# Backplane-3.net
KiCad netlist of a schematic drawn in EAGLE
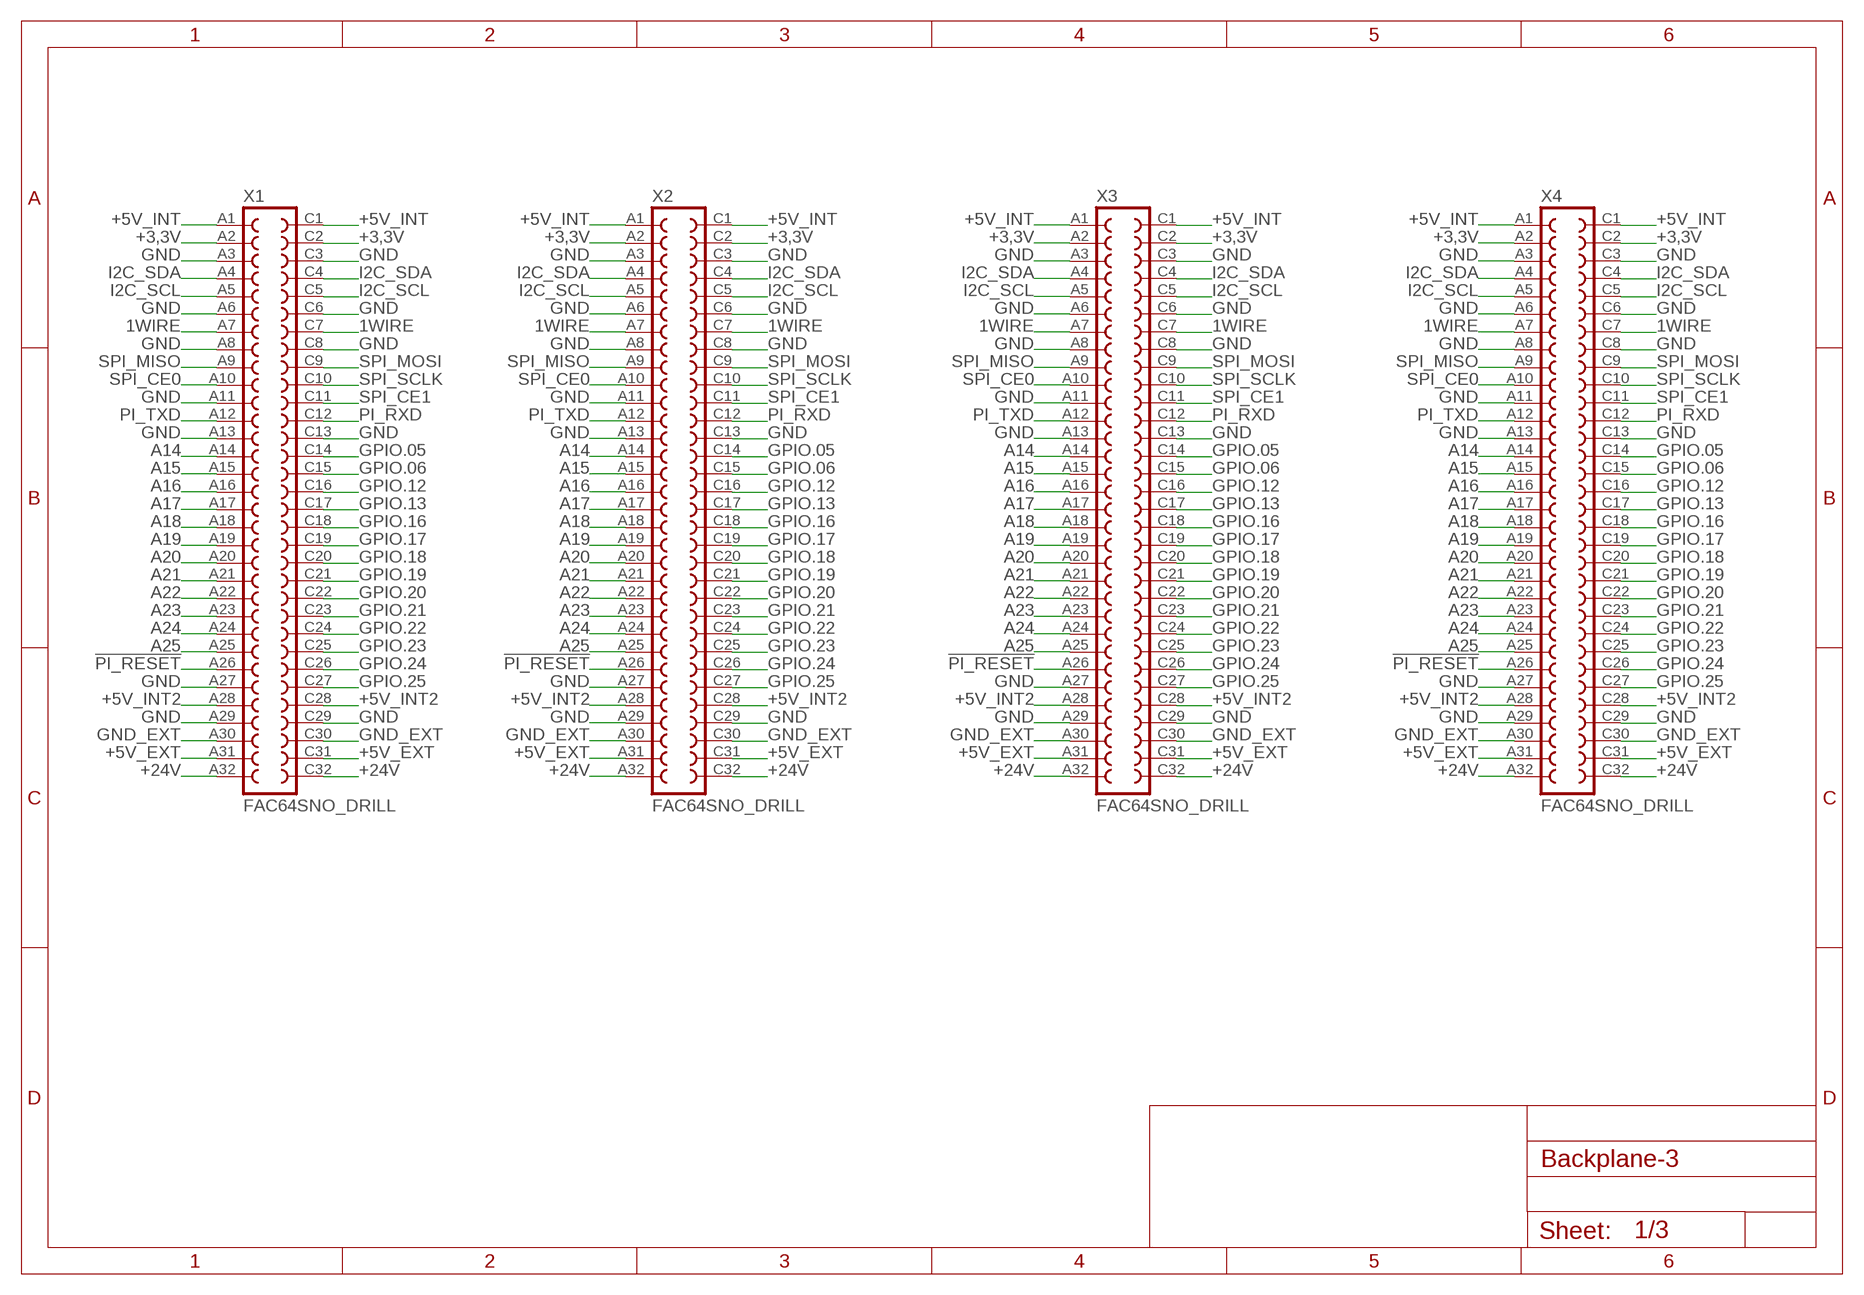
[diagram p0: schematic, sheet 1]
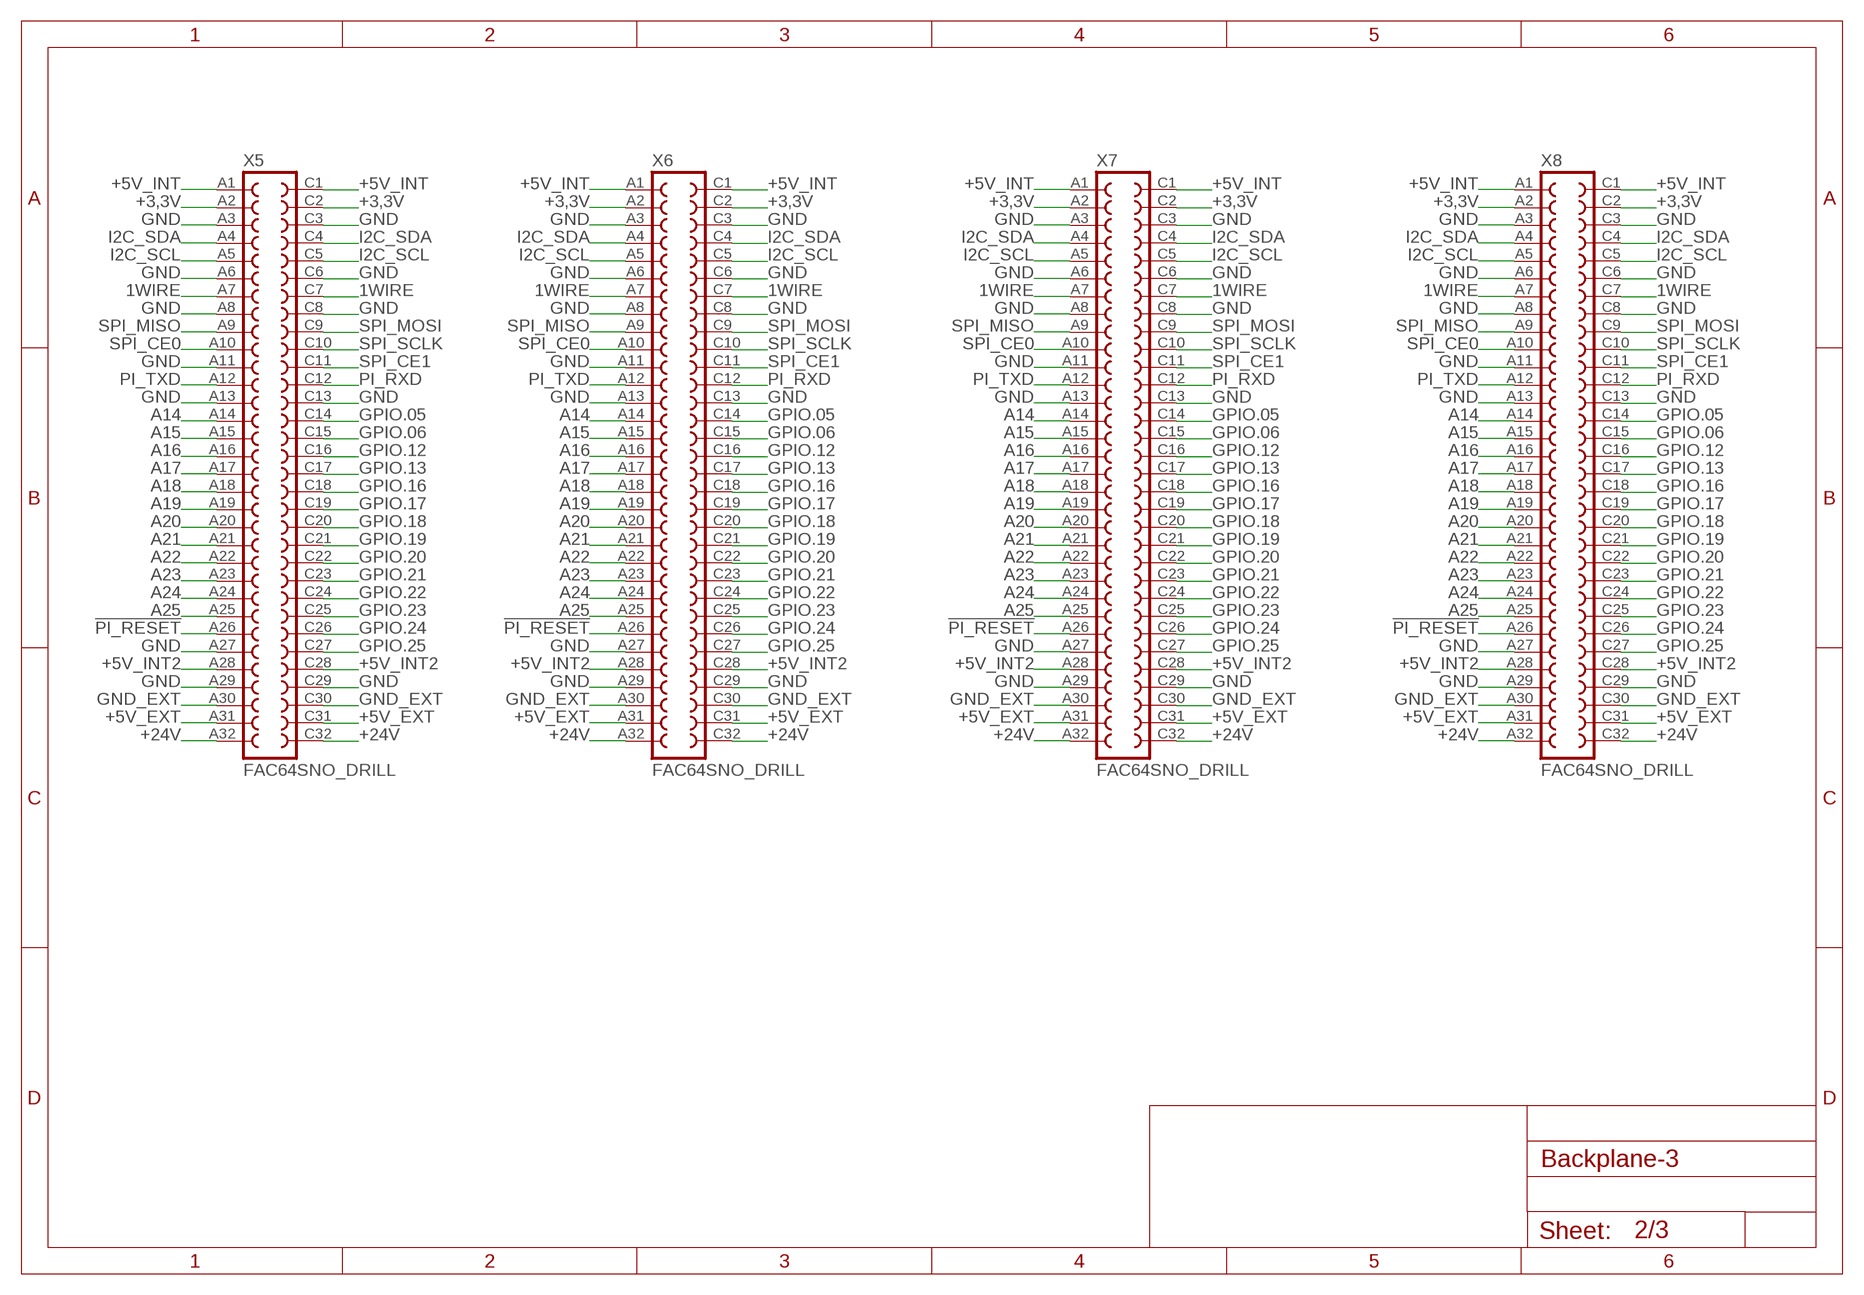
[diagram p1: schematic, sheet 2]
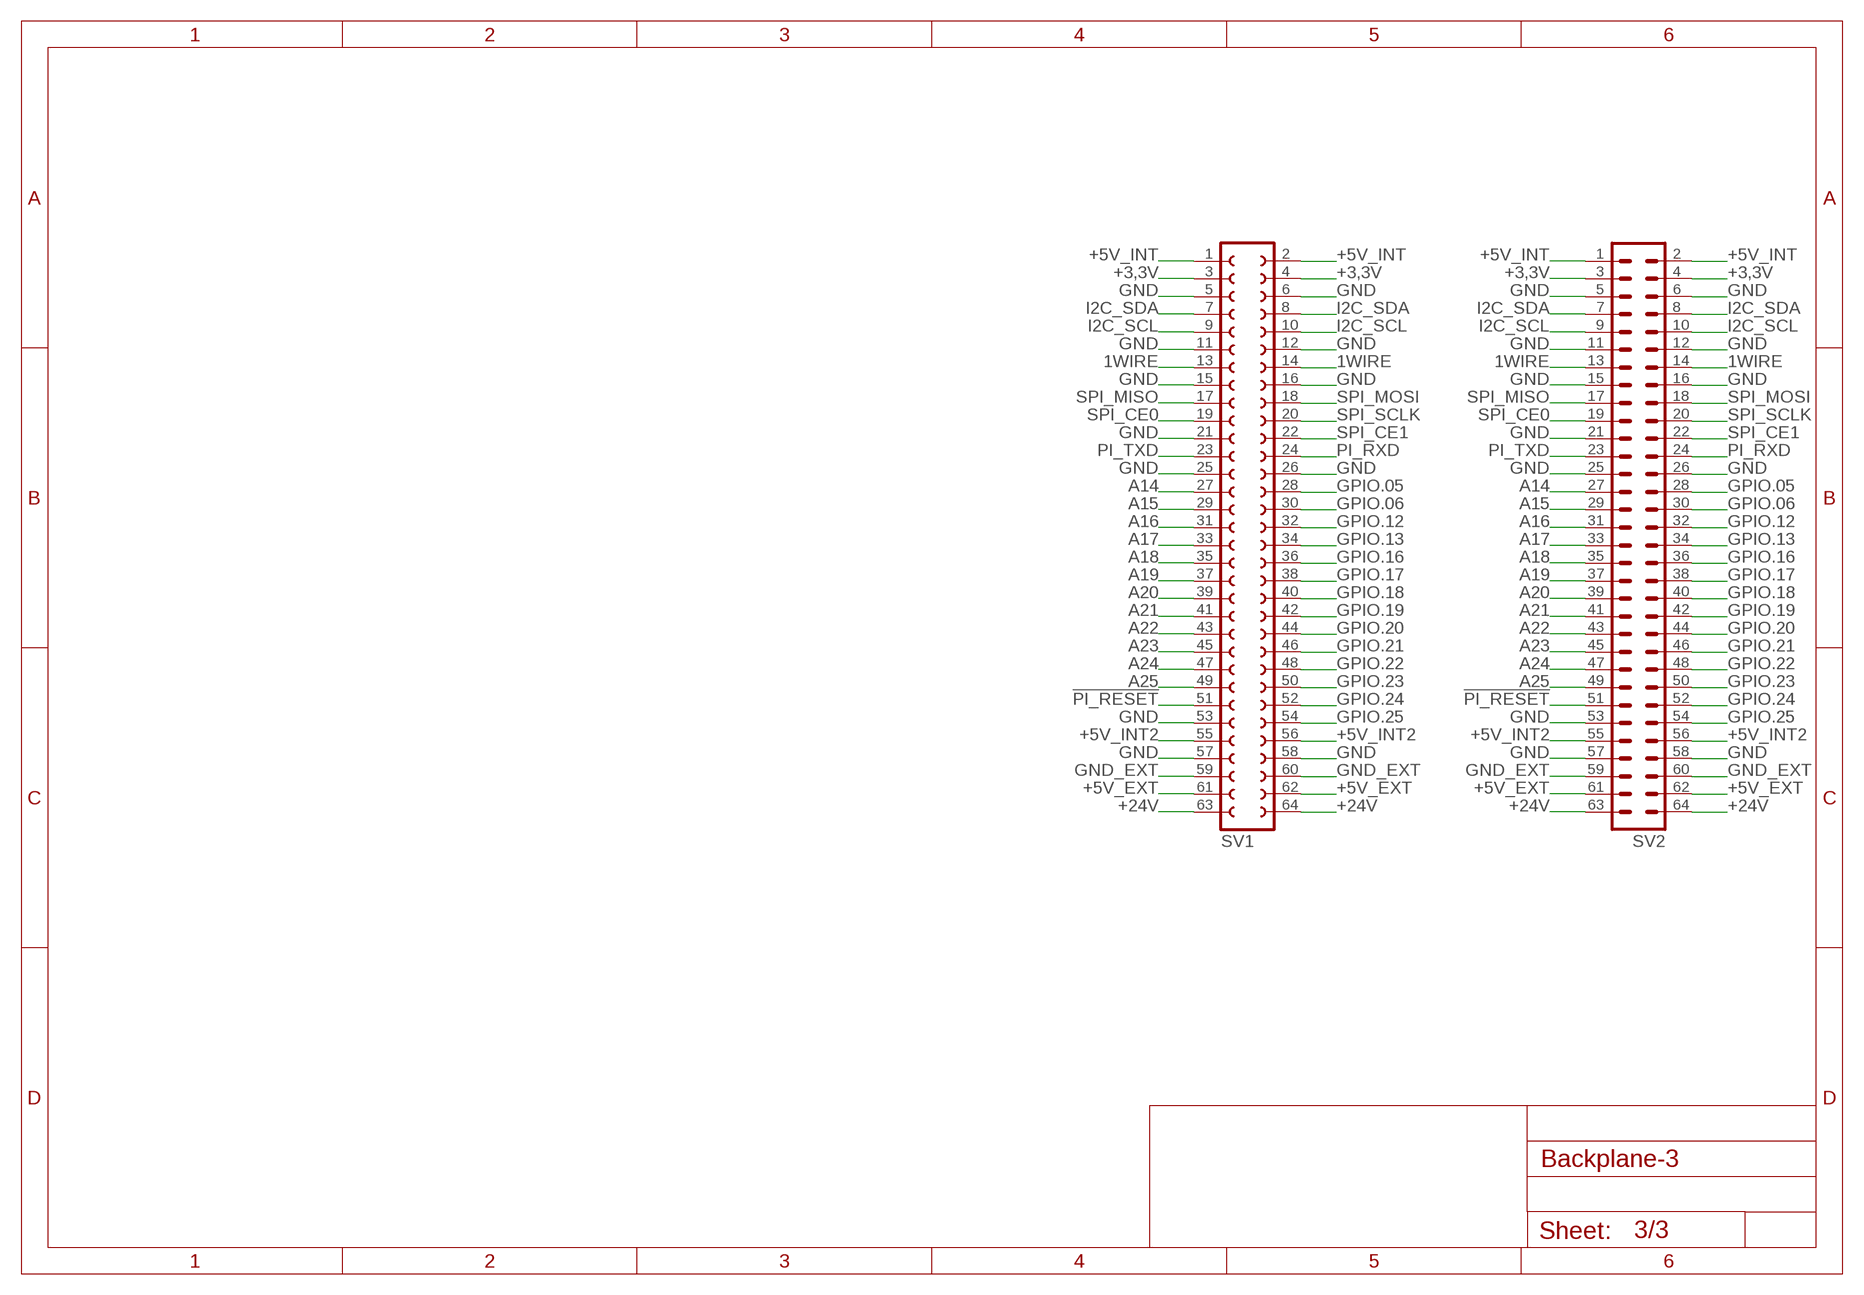
[diagram p2: schematic, sheet 3]

(export (version "E")
  (design (tool "Eeschema 10.0.6"))
  (components
    (comp (ref "X5")
      (value "FAC64SNO_DRILL")
      (footprint "eagle-import:FAC64S_NO_DRILL")
      (libsource (lib "eagle-import") (part "FAC64SNO_DRILL"))
    )
    (comp (ref "X6")
      (value "FAC64SNO_DRILL")
      (footprint "eagle-import:FAC64S_NO_DRILL")
      (libsource (lib "eagle-import") (part "FAC64SNO_DRILL"))
    )
    (comp (ref "X7")
      (value "FAC64SNO_DRILL")
      (footprint "eagle-import:FAC64S_NO_DRILL")
      (libsource (lib "eagle-import") (part "FAC64SNO_DRILL"))
    )
    (comp (ref "X8")
      (value "FAC64SNO_DRILL")
      (footprint "eagle-import:FAC64S_NO_DRILL")
      (libsource (lib "eagle-import") (part "FAC64SNO_DRILL"))
    )
    (comp (ref "SV1")
      (value "FE32-2W")
      (footprint "eagle-import:FE32-2W")
      (libsource (lib "eagle-import") (part "FE32-2W"))
    )
    (comp (ref "SV2")
      (value "MA32-2W")
      (footprint "eagle-import:MA32-2W")
      (libsource (lib "eagle-import") (part "MA32-2W"))
    )
    (comp (ref "X1")
      (value "FAC64SNO_DRILL")
      (footprint "eagle-import:FAC64S_NO_DRILL")
      (libsource (lib "eagle-import") (part "FAC64SNO_DRILL"))
    )
    (comp (ref "X2")
      (value "FAC64SNO_DRILL")
      (footprint "eagle-import:FAC64S_NO_DRILL")
      (libsource (lib "eagle-import") (part "FAC64SNO_DRILL"))
    )
    (comp (ref "X3")
      (value "FAC64SNO_DRILL")
      (footprint "eagle-import:FAC64S_NO_DRILL")
      (libsource (lib "eagle-import") (part "FAC64SNO_DRILL"))
    )
    (comp (ref "X4")
      (value "FAC64SNO_DRILL")
      (footprint "eagle-import:FAC64S_NO_DRILL")
      (libsource (lib "eagle-import") (part "FAC64SNO_DRILL"))
    )
  )
  (nets
    (net (code "1") (name "+3,3V") (class "Default")
      (node (ref "SV1") (pin "3") (pinfunction "3_3") (pintype "passive"))
      (node (ref "SV1") (pin "4") (pinfunction "4_4") (pintype "passive"))
      (node (ref "SV2") (pin "3") (pinfunction "3_3") (pintype "passive"))
      (node (ref "SV2") (pin "4") (pinfunction "4_4") (pintype "passive"))
      (node (ref "X1") (pin "A2") (pinfunction "A2_A2") (pintype "passive"))
      (node (ref "X1") (pin "C2") (pinfunction "C2_C2") (pintype "passive"))
      (node (ref "X2") (pin "A2") (pinfunction "A2_A2") (pintype "passive"))
      (node (ref "X2") (pin "C2") (pinfunction "C2_C2") (pintype "passive"))
      (node (ref "X3") (pin "A2") (pinfunction "A2_A2") (pintype "passive"))
      (node (ref "X3") (pin "C2") (pinfunction "C2_C2") (pintype "passive"))
      (node (ref "X4") (pin "A2") (pinfunction "A2_A2") (pintype "passive"))
      (node (ref "X4") (pin "C2") (pinfunction "C2_C2") (pintype "passive"))
      (node (ref "X5") (pin "A2") (pinfunction "A2_A2") (pintype "passive"))
      (node (ref "X5") (pin "C2") (pinfunction "C2_C2") (pintype "passive"))
      (node (ref "X6") (pin "A2") (pinfunction "A2_A2") (pintype "passive"))
      (node (ref "X6") (pin "C2") (pinfunction "C2_C2") (pintype "passive"))
      (node (ref "X7") (pin "A2") (pinfunction "A2_A2") (pintype "passive"))
      (node (ref "X7") (pin "C2") (pinfunction "C2_C2") (pintype "passive"))
      (node (ref "X8") (pin "A2") (pinfunction "A2_A2") (pintype "passive"))
      (node (ref "X8") (pin "C2") (pinfunction "C2_C2") (pintype "passive"))
    )
    (net (code "2") (name "+5V_EXT") (class "Default")
      (node (ref "SV1") (pin "61") (pinfunction "61_61") (pintype "passive"))
      (node (ref "SV1") (pin "62") (pinfunction "62_62") (pintype "passive"))
      (node (ref "SV2") (pin "61") (pinfunction "61_61") (pintype "passive"))
      (node (ref "SV2") (pin "62") (pinfunction "62_62") (pintype "passive"))
      (node (ref "X1") (pin "A31") (pinfunction "A31_A31") (pintype "passive"))
      (node (ref "X1") (pin "C31") (pinfunction "C31_C31") (pintype "passive"))
      (node (ref "X2") (pin "A31") (pinfunction "A31_A31") (pintype "passive"))
      (node (ref "X2") (pin "C31") (pinfunction "C31_C31") (pintype "passive"))
      (node (ref "X3") (pin "A31") (pinfunction "A31_A31") (pintype "passive"))
      (node (ref "X3") (pin "C31") (pinfunction "C31_C31") (pintype "passive"))
      (node (ref "X4") (pin "A31") (pinfunction "A31_A31") (pintype "passive"))
      (node (ref "X4") (pin "C31") (pinfunction "C31_C31") (pintype "passive"))
      (node (ref "X5") (pin "A31") (pinfunction "A31_A31") (pintype "passive"))
      (node (ref "X5") (pin "C31") (pinfunction "C31_C31") (pintype "passive"))
      (node (ref "X6") (pin "A31") (pinfunction "A31_A31") (pintype "passive"))
      (node (ref "X6") (pin "C31") (pinfunction "C31_C31") (pintype "passive"))
      (node (ref "X7") (pin "A31") (pinfunction "A31_A31") (pintype "passive"))
      (node (ref "X7") (pin "C31") (pinfunction "C31_C31") (pintype "passive"))
      (node (ref "X8") (pin "A31") (pinfunction "A31_A31") (pintype "passive"))
      (node (ref "X8") (pin "C31") (pinfunction "C31_C31") (pintype "passive"))
    )
    (net (code "3") (name "+5V_INT") (class "Default")
      (node (ref "SV1") (pin "1") (pinfunction "1_1") (pintype "passive"))
      (node (ref "SV1") (pin "2") (pinfunction "2_2") (pintype "passive"))
      (node (ref "SV2") (pin "1") (pinfunction "1_1") (pintype "passive"))
      (node (ref "SV2") (pin "2") (pinfunction "2_2") (pintype "passive"))
      (node (ref "X1") (pin "A1") (pinfunction "A1_A1") (pintype "passive"))
      (node (ref "X1") (pin "C1") (pinfunction "C1_C1") (pintype "passive"))
      (node (ref "X2") (pin "A1") (pinfunction "A1_A1") (pintype "passive"))
      (node (ref "X2") (pin "C1") (pinfunction "C1_C1") (pintype "passive"))
      (node (ref "X3") (pin "A1") (pinfunction "A1_A1") (pintype "passive"))
      (node (ref "X3") (pin "C1") (pinfunction "C1_C1") (pintype "passive"))
      (node (ref "X4") (pin "A1") (pinfunction "A1_A1") (pintype "passive"))
      (node (ref "X4") (pin "C1") (pinfunction "C1_C1") (pintype "passive"))
      (node (ref "X5") (pin "A1") (pinfunction "A1_A1") (pintype "passive"))
      (node (ref "X5") (pin "C1") (pinfunction "C1_C1") (pintype "passive"))
      (node (ref "X6") (pin "A1") (pinfunction "A1_A1") (pintype "passive"))
      (node (ref "X6") (pin "C1") (pinfunction "C1_C1") (pintype "passive"))
      (node (ref "X7") (pin "A1") (pinfunction "A1_A1") (pintype "passive"))
      (node (ref "X7") (pin "C1") (pinfunction "C1_C1") (pintype "passive"))
      (node (ref "X8") (pin "A1") (pinfunction "A1_A1") (pintype "passive"))
      (node (ref "X8") (pin "C1") (pinfunction "C1_C1") (pintype "passive"))
    )
    (net (code "4") (name "+5V_INT2") (class "Default")
      (node (ref "SV1") (pin "55") (pinfunction "55_55") (pintype "passive"))
      (node (ref "SV1") (pin "56") (pinfunction "56_56") (pintype "passive"))
      (node (ref "SV2") (pin "55") (pinfunction "55_55") (pintype "passive"))
      (node (ref "SV2") (pin "56") (pinfunction "56_56") (pintype "passive"))
      (node (ref "X1") (pin "A28") (pinfunction "A28_A28") (pintype "passive"))
      (node (ref "X1") (pin "C28") (pinfunction "C28_C28") (pintype "passive"))
      (node (ref "X2") (pin "A28") (pinfunction "A28_A28") (pintype "passive"))
      (node (ref "X2") (pin "C28") (pinfunction "C28_C28") (pintype "passive"))
      (node (ref "X3") (pin "A28") (pinfunction "A28_A28") (pintype "passive"))
      (node (ref "X3") (pin "C28") (pinfunction "C28_C28") (pintype "passive"))
      (node (ref "X4") (pin "A28") (pinfunction "A28_A28") (pintype "passive"))
      (node (ref "X4") (pin "C28") (pinfunction "C28_C28") (pintype "passive"))
      (node (ref "X5") (pin "A28") (pinfunction "A28_A28") (pintype "passive"))
      (node (ref "X5") (pin "C28") (pinfunction "C28_C28") (pintype "passive"))
      (node (ref "X6") (pin "A28") (pinfunction "A28_A28") (pintype "passive"))
      (node (ref "X6") (pin "C28") (pinfunction "C28_C28") (pintype "passive"))
      (node (ref "X7") (pin "A28") (pinfunction "A28_A28") (pintype "passive"))
      (node (ref "X7") (pin "C28") (pinfunction "C28_C28") (pintype "passive"))
      (node (ref "X8") (pin "A28") (pinfunction "A28_A28") (pintype "passive"))
      (node (ref "X8") (pin "C28") (pinfunction "C28_C28") (pintype "passive"))
    )
    (net (code "5") (name "+24V") (class "Default")
      (node (ref "SV1") (pin "63") (pinfunction "63_63") (pintype "passive"))
      (node (ref "SV1") (pin "64") (pinfunction "64_64") (pintype "passive"))
      (node (ref "SV2") (pin "63") (pinfunction "63_63") (pintype "passive"))
      (node (ref "SV2") (pin "64") (pinfunction "64_64") (pintype "passive"))
      (node (ref "X1") (pin "A32") (pinfunction "A32_A32") (pintype "passive"))
      (node (ref "X1") (pin "C32") (pinfunction "C32_C32") (pintype "passive"))
      (node (ref "X2") (pin "A32") (pinfunction "A32_A32") (pintype "passive"))
      (node (ref "X2") (pin "C32") (pinfunction "C32_C32") (pintype "passive"))
      (node (ref "X3") (pin "A32") (pinfunction "A32_A32") (pintype "passive"))
      (node (ref "X3") (pin "C32") (pinfunction "C32_C32") (pintype "passive"))
      (node (ref "X4") (pin "A32") (pinfunction "A32_A32") (pintype "passive"))
      (node (ref "X4") (pin "C32") (pinfunction "C32_C32") (pintype "passive"))
      (node (ref "X5") (pin "A32") (pinfunction "A32_A32") (pintype "passive"))
      (node (ref "X5") (pin "C32") (pinfunction "C32_C32") (pintype "passive"))
      (node (ref "X6") (pin "A32") (pinfunction "A32_A32") (pintype "passive"))
      (node (ref "X6") (pin "C32") (pinfunction "C32_C32") (pintype "passive"))
      (node (ref "X7") (pin "A32") (pinfunction "A32_A32") (pintype "passive"))
      (node (ref "X7") (pin "C32") (pinfunction "C32_C32") (pintype "passive"))
      (node (ref "X8") (pin "A32") (pinfunction "A32_A32") (pintype "passive"))
      (node (ref "X8") (pin "C32") (pinfunction "C32_C32") (pintype "passive"))
    )
    (net (code "6") (name "1WIRE") (class "Default")
      (node (ref "SV1") (pin "13") (pinfunction "13_13") (pintype "passive"))
      (node (ref "SV1") (pin "14") (pinfunction "14_14") (pintype "passive"))
      (node (ref "SV2") (pin "13") (pinfunction "13_13") (pintype "passive"))
      (node (ref "SV2") (pin "14") (pinfunction "14_14") (pintype "passive"))
      (node (ref "X1") (pin "A7") (pinfunction "A7_A7") (pintype "passive"))
      (node (ref "X1") (pin "C7") (pinfunction "C7_C7") (pintype "passive"))
      (node (ref "X2") (pin "A7") (pinfunction "A7_A7") (pintype "passive"))
      (node (ref "X2") (pin "C7") (pinfunction "C7_C7") (pintype "passive"))
      (node (ref "X3") (pin "A7") (pinfunction "A7_A7") (pintype "passive"))
      (node (ref "X3") (pin "C7") (pinfunction "C7_C7") (pintype "passive"))
      (node (ref "X4") (pin "A7") (pinfunction "A7_A7") (pintype "passive"))
      (node (ref "X4") (pin "C7") (pinfunction "C7_C7") (pintype "passive"))
      (node (ref "X5") (pin "A7") (pinfunction "A7_A7") (pintype "passive"))
      (node (ref "X5") (pin "C7") (pinfunction "C7_C7") (pintype "passive"))
      (node (ref "X6") (pin "A7") (pinfunction "A7_A7") (pintype "passive"))
      (node (ref "X6") (pin "C7") (pinfunction "C7_C7") (pintype "passive"))
      (node (ref "X7") (pin "A7") (pinfunction "A7_A7") (pintype "passive"))
      (node (ref "X7") (pin "C7") (pinfunction "C7_C7") (pintype "passive"))
      (node (ref "X8") (pin "A7") (pinfunction "A7_A7") (pintype "passive"))
      (node (ref "X8") (pin "C7") (pinfunction "C7_C7") (pintype "passive"))
    )
    (net (code "7") (name "A14") (class "Default")
      (node (ref "SV1") (pin "27") (pinfunction "27_27") (pintype "passive"))
      (node (ref "SV2") (pin "27") (pinfunction "27_27") (pintype "passive"))
      (node (ref "X1") (pin "A14") (pinfunction "A14_A14") (pintype "passive"))
      (node (ref "X2") (pin "A14") (pinfunction "A14_A14") (pintype "passive"))
      (node (ref "X3") (pin "A14") (pinfunction "A14_A14") (pintype "passive"))
      (node (ref "X4") (pin "A14") (pinfunction "A14_A14") (pintype "passive"))
      (node (ref "X5") (pin "A14") (pinfunction "A14_A14") (pintype "passive"))
      (node (ref "X6") (pin "A14") (pinfunction "A14_A14") (pintype "passive"))
      (node (ref "X7") (pin "A14") (pinfunction "A14_A14") (pintype "passive"))
      (node (ref "X8") (pin "A14") (pinfunction "A14_A14") (pintype "passive"))
    )
    (net (code "8") (name "A15") (class "Default")
      (node (ref "SV1") (pin "29") (pinfunction "29_29") (pintype "passive"))
      (node (ref "SV2") (pin "29") (pinfunction "29_29") (pintype "passive"))
      (node (ref "X1") (pin "A15") (pinfunction "A15_A15") (pintype "passive"))
      (node (ref "X2") (pin "A15") (pinfunction "A15_A15") (pintype "passive"))
      (node (ref "X3") (pin "A15") (pinfunction "A15_A15") (pintype "passive"))
      (node (ref "X4") (pin "A15") (pinfunction "A15_A15") (pintype "passive"))
      (node (ref "X5") (pin "A15") (pinfunction "A15_A15") (pintype "passive"))
      (node (ref "X6") (pin "A15") (pinfunction "A15_A15") (pintype "passive"))
      (node (ref "X7") (pin "A15") (pinfunction "A15_A15") (pintype "passive"))
      (node (ref "X8") (pin "A15") (pinfunction "A15_A15") (pintype "passive"))
    )
    (net (code "9") (name "A16") (class "Default")
      (node (ref "SV1") (pin "31") (pinfunction "31_31") (pintype "passive"))
      (node (ref "SV2") (pin "31") (pinfunction "31_31") (pintype "passive"))
      (node (ref "X1") (pin "A16") (pinfunction "A16_A16") (pintype "passive"))
      (node (ref "X2") (pin "A16") (pinfunction "A16_A16") (pintype "passive"))
      (node (ref "X3") (pin "A16") (pinfunction "A16_A16") (pintype "passive"))
      (node (ref "X4") (pin "A16") (pinfunction "A16_A16") (pintype "passive"))
      (node (ref "X5") (pin "A16") (pinfunction "A16_A16") (pintype "passive"))
      (node (ref "X6") (pin "A16") (pinfunction "A16_A16") (pintype "passive"))
      (node (ref "X7") (pin "A16") (pinfunction "A16_A16") (pintype "passive"))
      (node (ref "X8") (pin "A16") (pinfunction "A16_A16") (pintype "passive"))
    )
    (net (code "10") (name "A17") (class "Default")
      (node (ref "SV1") (pin "33") (pinfunction "33_33") (pintype "passive"))
      (node (ref "SV2") (pin "33") (pinfunction "33_33") (pintype "passive"))
      (node (ref "X1") (pin "A17") (pinfunction "A17_A17") (pintype "passive"))
      (node (ref "X2") (pin "A17") (pinfunction "A17_A17") (pintype "passive"))
      (node (ref "X3") (pin "A17") (pinfunction "A17_A17") (pintype "passive"))
      (node (ref "X4") (pin "A17") (pinfunction "A17_A17") (pintype "passive"))
      (node (ref "X5") (pin "A17") (pinfunction "A17_A17") (pintype "passive"))
      (node (ref "X6") (pin "A17") (pinfunction "A17_A17") (pintype "passive"))
      (node (ref "X7") (pin "A17") (pinfunction "A17_A17") (pintype "passive"))
      (node (ref "X8") (pin "A17") (pinfunction "A17_A17") (pintype "passive"))
    )
    (net (code "11") (name "A18") (class "Default")
      (node (ref "SV1") (pin "35") (pinfunction "35_35") (pintype "passive"))
      (node (ref "SV2") (pin "35") (pinfunction "35_35") (pintype "passive"))
      (node (ref "X1") (pin "A18") (pinfunction "A18_A18") (pintype "passive"))
      (node (ref "X2") (pin "A18") (pinfunction "A18_A18") (pintype "passive"))
      (node (ref "X3") (pin "A18") (pinfunction "A18_A18") (pintype "passive"))
      (node (ref "X4") (pin "A18") (pinfunction "A18_A18") (pintype "passive"))
      (node (ref "X5") (pin "A18") (pinfunction "A18_A18") (pintype "passive"))
      (node (ref "X6") (pin "A18") (pinfunction "A18_A18") (pintype "passive"))
      (node (ref "X7") (pin "A18") (pinfunction "A18_A18") (pintype "passive"))
      (node (ref "X8") (pin "A18") (pinfunction "A18_A18") (pintype "passive"))
    )
    (net (code "12") (name "A19") (class "Default")
      (node (ref "SV1") (pin "37") (pinfunction "37_37") (pintype "passive"))
      (node (ref "SV2") (pin "37") (pinfunction "37_37") (pintype "passive"))
      (node (ref "X1") (pin "A19") (pinfunction "A19_A19") (pintype "passive"))
      (node (ref "X2") (pin "A19") (pinfunction "A19_A19") (pintype "passive"))
      (node (ref "X3") (pin "A19") (pinfunction "A19_A19") (pintype "passive"))
      (node (ref "X4") (pin "A19") (pinfunction "A19_A19") (pintype "passive"))
      (node (ref "X5") (pin "A19") (pinfunction "A19_A19") (pintype "passive"))
      (node (ref "X6") (pin "A19") (pinfunction "A19_A19") (pintype "passive"))
      (node (ref "X7") (pin "A19") (pinfunction "A19_A19") (pintype "passive"))
      (node (ref "X8") (pin "A19") (pinfunction "A19_A19") (pintype "passive"))
    )
    (net (code "13") (name "A20") (class "Default")
      (node (ref "SV1") (pin "39") (pinfunction "39_39") (pintype "passive"))
      (node (ref "SV2") (pin "39") (pinfunction "39_39") (pintype "passive"))
      (node (ref "X1") (pin "A20") (pinfunction "A20_A20") (pintype "passive"))
      (node (ref "X2") (pin "A20") (pinfunction "A20_A20") (pintype "passive"))
      (node (ref "X3") (pin "A20") (pinfunction "A20_A20") (pintype "passive"))
      (node (ref "X4") (pin "A20") (pinfunction "A20_A20") (pintype "passive"))
      (node (ref "X5") (pin "A20") (pinfunction "A20_A20") (pintype "passive"))
      (node (ref "X6") (pin "A20") (pinfunction "A20_A20") (pintype "passive"))
      (node (ref "X7") (pin "A20") (pinfunction "A20_A20") (pintype "passive"))
      (node (ref "X8") (pin "A20") (pinfunction "A20_A20") (pintype "passive"))
    )
    (net (code "14") (name "A21") (class "Default")
      (node (ref "SV1") (pin "41") (pinfunction "41_41") (pintype "passive"))
      (node (ref "SV2") (pin "41") (pinfunction "41_41") (pintype "passive"))
      (node (ref "X1") (pin "A21") (pinfunction "A21_A21") (pintype "passive"))
      (node (ref "X2") (pin "A21") (pinfunction "A21_A21") (pintype "passive"))
      (node (ref "X3") (pin "A21") (pinfunction "A21_A21") (pintype "passive"))
      (node (ref "X4") (pin "A21") (pinfunction "A21_A21") (pintype "passive"))
      (node (ref "X5") (pin "A21") (pinfunction "A21_A21") (pintype "passive"))
      (node (ref "X6") (pin "A21") (pinfunction "A21_A21") (pintype "passive"))
      (node (ref "X7") (pin "A21") (pinfunction "A21_A21") (pintype "passive"))
      (node (ref "X8") (pin "A21") (pinfunction "A21_A21") (pintype "passive"))
    )
    (net (code "15") (name "A22") (class "Default")
      (node (ref "SV1") (pin "43") (pinfunction "43_43") (pintype "passive"))
      (node (ref "SV2") (pin "43") (pinfunction "43_43") (pintype "passive"))
      (node (ref "X1") (pin "A22") (pinfunction "A22_A22") (pintype "passive"))
      (node (ref "X2") (pin "A22") (pinfunction "A22_A22") (pintype "passive"))
      (node (ref "X3") (pin "A22") (pinfunction "A22_A22") (pintype "passive"))
      (node (ref "X4") (pin "A22") (pinfunction "A22_A22") (pintype "passive"))
      (node (ref "X5") (pin "A22") (pinfunction "A22_A22") (pintype "passive"))
      (node (ref "X6") (pin "A22") (pinfunction "A22_A22") (pintype "passive"))
      (node (ref "X7") (pin "A22") (pinfunction "A22_A22") (pintype "passive"))
      (node (ref "X8") (pin "A22") (pinfunction "A22_A22") (pintype "passive"))
    )
    (net (code "16") (name "A23") (class "Default")
      (node (ref "SV1") (pin "45") (pinfunction "45_45") (pintype "passive"))
      (node (ref "SV2") (pin "45") (pinfunction "45_45") (pintype "passive"))
      (node (ref "X1") (pin "A23") (pinfunction "A23_A23") (pintype "passive"))
      (node (ref "X2") (pin "A23") (pinfunction "A23_A23") (pintype "passive"))
      (node (ref "X3") (pin "A23") (pinfunction "A23_A23") (pintype "passive"))
      (node (ref "X4") (pin "A23") (pinfunction "A23_A23") (pintype "passive"))
      (node (ref "X5") (pin "A23") (pinfunction "A23_A23") (pintype "passive"))
      (node (ref "X6") (pin "A23") (pinfunction "A23_A23") (pintype "passive"))
      (node (ref "X7") (pin "A23") (pinfunction "A23_A23") (pintype "passive"))
      (node (ref "X8") (pin "A23") (pinfunction "A23_A23") (pintype "passive"))
    )
    (net (code "17") (name "A24") (class "Default")
      (node (ref "SV1") (pin "47") (pinfunction "47_47") (pintype "passive"))
      (node (ref "SV2") (pin "47") (pinfunction "47_47") (pintype "passive"))
      (node (ref "X1") (pin "A24") (pinfunction "A24_A24") (pintype "passive"))
      (node (ref "X2") (pin "A24") (pinfunction "A24_A24") (pintype "passive"))
      (node (ref "X3") (pin "A24") (pinfunction "A24_A24") (pintype "passive"))
      (node (ref "X4") (pin "A24") (pinfunction "A24_A24") (pintype "passive"))
      (node (ref "X5") (pin "A24") (pinfunction "A24_A24") (pintype "passive"))
      (node (ref "X6") (pin "A24") (pinfunction "A24_A24") (pintype "passive"))
      (node (ref "X7") (pin "A24") (pinfunction "A24_A24") (pintype "passive"))
      (node (ref "X8") (pin "A24") (pinfunction "A24_A24") (pintype "passive"))
    )
    (net (code "18") (name "A25") (class "Default")
      (node (ref "SV1") (pin "49") (pinfunction "49_49") (pintype "passive"))
      (node (ref "SV2") (pin "49") (pinfunction "49_49") (pintype "passive"))
      (node (ref "X1") (pin "A25") (pinfunction "A25_A25") (pintype "passive"))
      (node (ref "X2") (pin "A25") (pinfunction "A25_A25") (pintype "passive"))
      (node (ref "X3") (pin "A25") (pinfunction "A25_A25") (pintype "passive"))
      (node (ref "X4") (pin "A25") (pinfunction "A25_A25") (pintype "passive"))
      (node (ref "X5") (pin "A25") (pinfunction "A25_A25") (pintype "passive"))
      (node (ref "X6") (pin "A25") (pinfunction "A25_A25") (pintype "passive"))
      (node (ref "X7") (pin "A25") (pinfunction "A25_A25") (pintype "passive"))
      (node (ref "X8") (pin "A25") (pinfunction "A25_A25") (pintype "passive"))
    )
    (net (code "19") (name "GND") (class "Default")
      (node (ref "SV1") (pin "11") (pinfunction "11_11") (pintype "passive"))
      (node (ref "SV1") (pin "12") (pinfunction "12_12") (pintype "passive"))
      (node (ref "SV1") (pin "15") (pinfunction "15_15") (pintype "passive"))
      (node (ref "SV1") (pin "16") (pinfunction "16_16") (pintype "passive"))
      (node (ref "SV1") (pin "21") (pinfunction "21_21") (pintype "passive"))
      (node (ref "SV1") (pin "25") (pinfunction "25_25") (pintype "passive"))
      (node (ref "SV1") (pin "26") (pinfunction "26_26") (pintype "passive"))
      (node (ref "SV1") (pin "5") (pinfunction "5_5") (pintype "passive"))
      (node (ref "SV1") (pin "53") (pinfunction "53_53") (pintype "passive"))
      (node (ref "SV1") (pin "57") (pinfunction "57_57") (pintype "passive"))
      (node (ref "SV1") (pin "58") (pinfunction "58_58") (pintype "passive"))
      (node (ref "SV1") (pin "6") (pinfunction "6_6") (pintype "passive"))
      (node (ref "SV2") (pin "11") (pinfunction "11_11") (pintype "passive"))
      (node (ref "SV2") (pin "12") (pinfunction "12_12") (pintype "passive"))
      (node (ref "SV2") (pin "15") (pinfunction "15_15") (pintype "passive"))
      (node (ref "SV2") (pin "16") (pinfunction "16_16") (pintype "passive"))
      (node (ref "SV2") (pin "21") (pinfunction "21_21") (pintype "passive"))
      (node (ref "SV2") (pin "25") (pinfunction "25_25") (pintype "passive"))
      (node (ref "SV2") (pin "26") (pinfunction "26_26") (pintype "passive"))
      (node (ref "SV2") (pin "5") (pinfunction "5_5") (pintype "passive"))
      (node (ref "SV2") (pin "53") (pinfunction "53_53") (pintype "passive"))
      (node (ref "SV2") (pin "57") (pinfunction "57_57") (pintype "passive"))
      (node (ref "SV2") (pin "58") (pinfunction "58_58") (pintype "passive"))
      (node (ref "SV2") (pin "6") (pinfunction "6_6") (pintype "passive"))
      (node (ref "X1") (pin "A11") (pinfunction "A11_A11") (pintype "passive"))
      (node (ref "X1") (pin "A13") (pinfunction "A13_A13") (pintype "passive"))
      (node (ref "X1") (pin "A27") (pinfunction "A27_A27") (pintype "passive"))
      (node (ref "X1") (pin "A29") (pinfunction "A29_A29") (pintype "passive"))
      (node (ref "X1") (pin "A3") (pinfunction "A3_A3") (pintype "passive"))
      (node (ref "X1") (pin "A6") (pinfunction "A6_A6") (pintype "passive"))
      (node (ref "X1") (pin "A8") (pinfunction "A8_A8") (pintype "passive"))
      (node (ref "X1") (pin "C13") (pinfunction "C13_C13") (pintype "passive"))
      (node (ref "X1") (pin "C29") (pinfunction "C29_C29") (pintype "passive"))
      (node (ref "X1") (pin "C3") (pinfunction "C3_C3") (pintype "passive"))
      (node (ref "X1") (pin "C6") (pinfunction "C6_C6") (pintype "passive"))
      (node (ref "X1") (pin "C8") (pinfunction "C8_C8") (pintype "passive"))
      (node (ref "X2") (pin "A11") (pinfunction "A11_A11") (pintype "passive"))
      (node (ref "X2") (pin "A13") (pinfunction "A13_A13") (pintype "passive"))
      (node (ref "X2") (pin "A27") (pinfunction "A27_A27") (pintype "passive"))
      (node (ref "X2") (pin "A29") (pinfunction "A29_A29") (pintype "passive"))
      (node (ref "X2") (pin "A3") (pinfunction "A3_A3") (pintype "passive"))
      (node (ref "X2") (pin "A6") (pinfunction "A6_A6") (pintype "passive"))
      (node (ref "X2") (pin "A8") (pinfunction "A8_A8") (pintype "passive"))
      (node (ref "X2") (pin "C13") (pinfunction "C13_C13") (pintype "passive"))
      (node (ref "X2") (pin "C29") (pinfunction "C29_C29") (pintype "passive"))
      (node (ref "X2") (pin "C3") (pinfunction "C3_C3") (pintype "passive"))
      (node (ref "X2") (pin "C6") (pinfunction "C6_C6") (pintype "passive"))
      (node (ref "X2") (pin "C8") (pinfunction "C8_C8") (pintype "passive"))
      (node (ref "X3") (pin "A11") (pinfunction "A11_A11") (pintype "passive"))
      (node (ref "X3") (pin "A13") (pinfunction "A13_A13") (pintype "passive"))
      (node (ref "X3") (pin "A27") (pinfunction "A27_A27") (pintype "passive"))
      (node (ref "X3") (pin "A29") (pinfunction "A29_A29") (pintype "passive"))
      (node (ref "X3") (pin "A3") (pinfunction "A3_A3") (pintype "passive"))
      (node (ref "X3") (pin "A6") (pinfunction "A6_A6") (pintype "passive"))
      (node (ref "X3") (pin "A8") (pinfunction "A8_A8") (pintype "passive"))
      (node (ref "X3") (pin "C13") (pinfunction "C13_C13") (pintype "passive"))
      (node (ref "X3") (pin "C29") (pinfunction "C29_C29") (pintype "passive"))
      (node (ref "X3") (pin "C3") (pinfunction "C3_C3") (pintype "passive"))
      (node (ref "X3") (pin "C6") (pinfunction "C6_C6") (pintype "passive"))
      (node (ref "X3") (pin "C8") (pinfunction "C8_C8") (pintype "passive"))
      (node (ref "X4") (pin "A11") (pinfunction "A11_A11") (pintype "passive"))
      (node (ref "X4") (pin "A13") (pinfunction "A13_A13") (pintype "passive"))
      (node (ref "X4") (pin "A27") (pinfunction "A27_A27") (pintype "passive"))
      (node (ref "X4") (pin "A29") (pinfunction "A29_A29") (pintype "passive"))
      (node (ref "X4") (pin "A3") (pinfunction "A3_A3") (pintype "passive"))
      (node (ref "X4") (pin "A6") (pinfunction "A6_A6") (pintype "passive"))
      (node (ref "X4") (pin "A8") (pinfunction "A8_A8") (pintype "passive"))
      (node (ref "X4") (pin "C13") (pinfunction "C13_C13") (pintype "passive"))
      (node (ref "X4") (pin "C29") (pinfunction "C29_C29") (pintype "passive"))
      (node (ref "X4") (pin "C3") (pinfunction "C3_C3") (pintype "passive"))
      (node (ref "X4") (pin "C6") (pinfunction "C6_C6") (pintype "passive"))
      (node (ref "X4") (pin "C8") (pinfunction "C8_C8") (pintype "passive"))
      (node (ref "X5") (pin "A11") (pinfunction "A11_A11") (pintype "passive"))
      (node (ref "X5") (pin "A13") (pinfunction "A13_A13") (pintype "passive"))
      (node (ref "X5") (pin "A27") (pinfunction "A27_A27") (pintype "passive"))
      (node (ref "X5") (pin "A29") (pinfunction "A29_A29") (pintype "passive"))
      (node (ref "X5") (pin "A3") (pinfunction "A3_A3") (pintype "passive"))
      (node (ref "X5") (pin "A6") (pinfunction "A6_A6") (pintype "passive"))
      (node (ref "X5") (pin "A8") (pinfunction "A8_A8") (pintype "passive"))
      (node (ref "X5") (pin "C13") (pinfunction "C13_C13") (pintype "passive"))
      (node (ref "X5") (pin "C29") (pinfunction "C29_C29") (pintype "passive"))
      (node (ref "X5") (pin "C3") (pinfunction "C3_C3") (pintype "passive"))
      (node (ref "X5") (pin "C6") (pinfunction "C6_C6") (pintype "passive"))
      (node (ref "X5") (pin "C8") (pinfunction "C8_C8") (pintype "passive"))
      (node (ref "X6") (pin "A11") (pinfunction "A11_A11") (pintype "passive"))
      (node (ref "X6") (pin "A13") (pinfunction "A13_A13") (pintype "passive"))
      (node (ref "X6") (pin "A27") (pinfunction "A27_A27") (pintype "passive"))
      (node (ref "X6") (pin "A29") (pinfunction "A29_A29") (pintype "passive"))
      (node (ref "X6") (pin "A3") (pinfunction "A3_A3") (pintype "passive"))
      (node (ref "X6") (pin "A6") (pinfunction "A6_A6") (pintype "passive"))
      (node (ref "X6") (pin "A8") (pinfunction "A8_A8") (pintype "passive"))
      (node (ref "X6") (pin "C13") (pinfunction "C13_C13") (pintype "passive"))
      (node (ref "X6") (pin "C29") (pinfunction "C29_C29") (pintype "passive"))
      (node (ref "X6") (pin "C3") (pinfunction "C3_C3") (pintype "passive"))
      (node (ref "X6") (pin "C6") (pinfunction "C6_C6") (pintype "passive"))
      (node (ref "X6") (pin "C8") (pinfunction "C8_C8") (pintype "passive"))
      (node (ref "X7") (pin "A11") (pinfunction "A11_A11") (pintype "passive"))
      (node (ref "X7") (pin "A13") (pinfunction "A13_A13") (pintype "passive"))
      (node (ref "X7") (pin "A27") (pinfunction "A27_A27") (pintype "passive"))
      (node (ref "X7") (pin "A29") (pinfunction "A29_A29") (pintype "passive"))
      (node (ref "X7") (pin "A3") (pinfunction "A3_A3") (pintype "passive"))
      (node (ref "X7") (pin "A6") (pinfunction "A6_A6") (pintype "passive"))
      (node (ref "X7") (pin "A8") (pinfunction "A8_A8") (pintype "passive"))
      (node (ref "X7") (pin "C13") (pinfunction "C13_C13") (pintype "passive"))
      (node (ref "X7") (pin "C29") (pinfunction "C29_C29") (pintype "passive"))
      (node (ref "X7") (pin "C3") (pinfunction "C3_C3") (pintype "passive"))
      (node (ref "X7") (pin "C6") (pinfunction "C6_C6") (pintype "passive"))
      (node (ref "X7") (pin "C8") (pinfunction "C8_C8") (pintype "passive"))
      (node (ref "X8") (pin "A11") (pinfunction "A11_A11") (pintype "passive"))
      (node (ref "X8") (pin "A13") (pinfunction "A13_A13") (pintype "passive"))
      (node (ref "X8") (pin "A27") (pinfunction "A27_A27") (pintype "passive"))
      (node (ref "X8") (pin "A29") (pinfunction "A29_A29") (pintype "passive"))
      (node (ref "X8") (pin "A3") (pinfunction "A3_A3") (pintype "passive"))
      (node (ref "X8") (pin "A6") (pinfunction "A6_A6") (pintype "passive"))
      (node (ref "X8") (pin "A8") (pinfunction "A8_A8") (pintype "passive"))
      (node (ref "X8") (pin "C13") (pinfunction "C13_C13") (pintype "passive"))
      (node (ref "X8") (pin "C29") (pinfunction "C29_C29") (pintype "passive"))
      (node (ref "X8") (pin "C3") (pinfunction "C3_C3") (pintype "passive"))
      (node (ref "X8") (pin "C6") (pinfunction "C6_C6") (pintype "passive"))
      (node (ref "X8") (pin "C8") (pinfunction "C8_C8") (pintype "passive"))
    )
    (net (code "20") (name "GND_EXT") (class "Default")
      (node (ref "SV1") (pin "59") (pinfunction "59_59") (pintype "passive"))
      (node (ref "SV1") (pin "60") (pinfunction "60_60") (pintype "passive"))
      (node (ref "SV2") (pin "59") (pinfunction "59_59") (pintype "passive"))
      (node (ref "SV2") (pin "60") (pinfunction "60_60") (pintype "passive"))
      (node (ref "X1") (pin "A30") (pinfunction "A30_A30") (pintype "passive"))
      (node (ref "X1") (pin "C30") (pinfunction "C30_C30") (pintype "passive"))
      (node (ref "X2") (pin "A30") (pinfunction "A30_A30") (pintype "passive"))
      (node (ref "X2") (pin "C30") (pinfunction "C30_C30") (pintype "passive"))
      (node (ref "X3") (pin "A30") (pinfunction "A30_A30") (pintype "passive"))
      (node (ref "X3") (pin "C30") (pinfunction "C30_C30") (pintype "passive"))
      (node (ref "X4") (pin "A30") (pinfunction "A30_A30") (pintype "passive"))
      (node (ref "X4") (pin "C30") (pinfunction "C30_C30") (pintype "passive"))
      (node (ref "X5") (pin "A30") (pinfunction "A30_A30") (pintype "passive"))
      (node (ref "X5") (pin "C30") (pinfunction "C30_C30") (pintype "passive"))
      (node (ref "X6") (pin "A30") (pinfunction "A30_A30") (pintype "passive"))
      (node (ref "X6") (pin "C30") (pinfunction "C30_C30") (pintype "passive"))
      (node (ref "X7") (pin "A30") (pinfunction "A30_A30") (pintype "passive"))
      (node (ref "X7") (pin "C30") (pinfunction "C30_C30") (pintype "passive"))
      (node (ref "X8") (pin "A30") (pinfunction "A30_A30") (pintype "passive"))
      (node (ref "X8") (pin "C30") (pinfunction "C30_C30") (pintype "passive"))
    )
    (net (code "21") (name "GPIO.05") (class "Default")
      (node (ref "SV1") (pin "28") (pinfunction "28_28") (pintype "passive"))
      (node (ref "SV2") (pin "28") (pinfunction "28_28") (pintype "passive"))
      (node (ref "X1") (pin "C14") (pinfunction "C14_C14") (pintype "passive"))
      (node (ref "X2") (pin "C14") (pinfunction "C14_C14") (pintype "passive"))
      (node (ref "X3") (pin "C14") (pinfunction "C14_C14") (pintype "passive"))
      (node (ref "X4") (pin "C14") (pinfunction "C14_C14") (pintype "passive"))
      (node (ref "X5") (pin "C14") (pinfunction "C14_C14") (pintype "passive"))
      (node (ref "X6") (pin "C14") (pinfunction "C14_C14") (pintype "passive"))
      (node (ref "X7") (pin "C14") (pinfunction "C14_C14") (pintype "passive"))
      (node (ref "X8") (pin "C14") (pinfunction "C14_C14") (pintype "passive"))
    )
    (net (code "22") (name "GPIO.06") (class "Default")
      (node (ref "SV1") (pin "30") (pinfunction "30_30") (pintype "passive"))
      (node (ref "SV2") (pin "30") (pinfunction "30_30") (pintype "passive"))
      (node (ref "X1") (pin "C15") (pinfunction "C15_C15") (pintype "passive"))
      (node (ref "X2") (pin "C15") (pinfunction "C15_C15") (pintype "passive"))
      (node (ref "X3") (pin "C15") (pinfunction "C15_C15") (pintype "passive"))
      (node (ref "X4") (pin "C15") (pinfunction "C15_C15") (pintype "passive"))
      (node (ref "X5") (pin "C15") (pinfunction "C15_C15") (pintype "passive"))
      (node (ref "X6") (pin "C15") (pinfunction "C15_C15") (pintype "passive"))
      (node (ref "X7") (pin "C15") (pinfunction "C15_C15") (pintype "passive"))
      (node (ref "X8") (pin "C15") (pinfunction "C15_C15") (pintype "passive"))
    )
    (net (code "23") (name "GPIO.12") (class "Default")
      (node (ref "SV1") (pin "32") (pinfunction "32_32") (pintype "passive"))
      (node (ref "SV2") (pin "32") (pinfunction "32_32") (pintype "passive"))
      (node (ref "X1") (pin "C16") (pinfunction "C16_C16") (pintype "passive"))
      (node (ref "X2") (pin "C16") (pinfunction "C16_C16") (pintype "passive"))
      (node (ref "X3") (pin "C16") (pinfunction "C16_C16") (pintype "passive"))
      (node (ref "X4") (pin "C16") (pinfunction "C16_C16") (pintype "passive"))
      (node (ref "X5") (pin "C16") (pinfunction "C16_C16") (pintype "passive"))
      (node (ref "X6") (pin "C16") (pinfunction "C16_C16") (pintype "passive"))
      (node (ref "X7") (pin "C16") (pinfunction "C16_C16") (pintype "passive"))
      (node (ref "X8") (pin "C16") (pinfunction "C16_C16") (pintype "passive"))
    )
    (net (code "24") (name "GPIO.13") (class "Default")
      (node (ref "SV1") (pin "34") (pinfunction "34_34") (pintype "passive"))
      (node (ref "SV2") (pin "34") (pinfunction "34_34") (pintype "passive"))
      (node (ref "X1") (pin "C17") (pinfunction "C17_C17") (pintype "passive"))
      (node (ref "X2") (pin "C17") (pinfunction "C17_C17") (pintype "passive"))
      (node (ref "X3") (pin "C17") (pinfunction "C17_C17") (pintype "passive"))
      (node (ref "X4") (pin "C17") (pinfunction "C17_C17") (pintype "passive"))
      (node (ref "X5") (pin "C17") (pinfunction "C17_C17") (pintype "passive"))
      (node (ref "X6") (pin "C17") (pinfunction "C17_C17") (pintype "passive"))
      (node (ref "X7") (pin "C17") (pinfunction "C17_C17") (pintype "passive"))
      (node (ref "X8") (pin "C17") (pinfunction "C17_C17") (pintype "passive"))
    )
    (net (code "25") (name "GPIO.16") (class "Default")
      (node (ref "SV1") (pin "36") (pinfunction "36_36") (pintype "passive"))
      (node (ref "SV2") (pin "36") (pinfunction "36_36") (pintype "passive"))
      (node (ref "X1") (pin "C18") (pinfunction "C18_C18") (pintype "passive"))
      (node (ref "X2") (pin "C18") (pinfunction "C18_C18") (pintype "passive"))
      (node (ref "X3") (pin "C18") (pinfunction "C18_C18") (pintype "passive"))
      (node (ref "X4") (pin "C18") (pinfunction "C18_C18") (pintype "passive"))
      (node (ref "X5") (pin "C18") (pinfunction "C18_C18") (pintype "passive"))
      (node (ref "X6") (pin "C18") (pinfunction "C18_C18") (pintype "passive"))
      (node (ref "X7") (pin "C18") (pinfunction "C18_C18") (pintype "passive"))
      (node (ref "X8") (pin "C18") (pinfunction "C18_C18") (pintype "passive"))
    )
    (net (code "26") (name "GPIO.17") (class "Default")
      (node (ref "SV1") (pin "38") (pinfunction "38_38") (pintype "passive"))
      (node (ref "SV2") (pin "38") (pinfunction "38_38") (pintype "passive"))
      (node (ref "X1") (pin "C19") (pinfunction "C19_C19") (pintype "passive"))
      (node (ref "X2") (pin "C19") (pinfunction "C19_C19") (pintype "passive"))
      (node (ref "X3") (pin "C19") (pinfunction "C19_C19") (pintype "passive"))
      (node (ref "X4") (pin "C19") (pinfunction "C19_C19") (pintype "passive"))
      (node (ref "X5") (pin "C19") (pinfunction "C19_C19") (pintype "passive"))
      (node (ref "X6") (pin "C19") (pinfunction "C19_C19") (pintype "passive"))
      (node (ref "X7") (pin "C19") (pinfunction "C19_C19") (pintype "passive"))
      (node (ref "X8") (pin "C19") (pinfunction "C19_C19") (pintype "passive"))
    )
    (net (code "27") (name "GPIO.18") (class "Default")
      (node (ref "SV1") (pin "40") (pinfunction "40_40") (pintype "passive"))
      (node (ref "SV2") (pin "40") (pinfunction "40_40") (pintype "passive"))
      (node (ref "X1") (pin "C20") (pinfunction "C20_C20") (pintype "passive"))
      (node (ref "X2") (pin "C20") (pinfunction "C20_C20") (pintype "passive"))
      (node (ref "X3") (pin "C20") (pinfunction "C20_C20") (pintype "passive"))
      (node (ref "X4") (pin "C20") (pinfunction "C20_C20") (pintype "passive"))
      (node (ref "X5") (pin "C20") (pinfunction "C20_C20") (pintype "passive"))
      (node (ref "X6") (pin "C20") (pinfunction "C20_C20") (pintype "passive"))
      (node (ref "X7") (pin "C20") (pinfunction "C20_C20") (pintype "passive"))
      (node (ref "X8") (pin "C20") (pinfunction "C20_C20") (pintype "passive"))
    )
    (net (code "28") (name "GPIO.19") (class "Default")
      (node (ref "SV1") (pin "42") (pinfunction "42_42") (pintype "passive"))
      (node (ref "SV2") (pin "42") (pinfunction "42_42") (pintype "passive"))
      (node (ref "X1") (pin "C21") (pinfunction "C21_C21") (pintype "passive"))
      (node (ref "X2") (pin "C21") (pinfunction "C21_C21") (pintype "passive"))
      (node (ref "X3") (pin "C21") (pinfunction "C21_C21") (pintype "passive"))
      (node (ref "X4") (pin "C21") (pinfunction "C21_C21") (pintype "passive"))
      (node (ref "X5") (pin "C21") (pinfunction "C21_C21") (pintype "passive"))
      (node (ref "X6") (pin "C21") (pinfunction "C21_C21") (pintype "passive"))
      (node (ref "X7") (pin "C21") (pinfunction "C21_C21") (pintype "passive"))
      (node (ref "X8") (pin "C21") (pinfunction "C21_C21") (pintype "passive"))
    )
    (net (code "29") (name "GPIO.20") (class "Default")
      (node (ref "SV1") (pin "44") (pinfunction "44_44") (pintype "passive"))
      (node (ref "SV2") (pin "44") (pinfunction "44_44") (pintype "passive"))
      (node (ref "X1") (pin "C22") (pinfunction "C22_C22") (pintype "passive"))
      (node (ref "X2") (pin "C22") (pinfunction "C22_C22") (pintype "passive"))
      (node (ref "X3") (pin "C22") (pinfunction "C22_C22") (pintype "passive"))
      (node (ref "X4") (pin "C22") (pinfunction "C22_C22") (pintype "passive"))
      (node (ref "X5") (pin "C22") (pinfunction "C22_C22") (pintype "passive"))
      (node (ref "X6") (pin "C22") (pinfunction "C22_C22") (pintype "passive"))
      (node (ref "X7") (pin "C22") (pinfunction "C22_C22") (pintype "passive"))
      (node (ref "X8") (pin "C22") (pinfunction "C22_C22") (pintype "passive"))
    )
    (net (code "30") (name "GPIO.21") (class "Default")
      (node (ref "SV1") (pin "46") (pinfunction "46_46") (pintype "passive"))
      (node (ref "SV2") (pin "46") (pinfunction "46_46") (pintype "passive"))
      (node (ref "X1") (pin "C23") (pinfunction "C23_C23") (pintype "passive"))
      (node (ref "X2") (pin "C23") (pinfunction "C23_C23") (pintype "passive"))
      (node (ref "X3") (pin "C23") (pinfunction "C23_C23") (pintype "passive"))
      (node (ref "X4") (pin "C23") (pinfunction "C23_C23") (pintype "passive"))
      (node (ref "X5") (pin "C23") (pinfunction "C23_C23") (pintype "passive"))
      (node (ref "X6") (pin "C23") (pinfunction "C23_C23") (pintype "passive"))
      (node (ref "X7") (pin "C23") (pinfunction "C23_C23") (pintype "passive"))
      (node (ref "X8") (pin "C23") (pinfunction "C23_C23") (pintype "passive"))
    )
    (net (code "31") (name "GPIO.22") (class "Default")
      (node (ref "SV1") (pin "48") (pinfunction "48_48") (pintype "passive"))
      (node (ref "SV2") (pin "48") (pinfunction "48_48") (pintype "passive"))
      (node (ref "X1") (pin "C24") (pinfunction "C24_C24") (pintype "passive"))
      (node (ref "X2") (pin "C24") (pinfunction "C24_C24") (pintype "passive"))
      (node (ref "X3") (pin "C24") (pinfunction "C24_C24") (pintype "passive"))
      (node (ref "X4") (pin "C24") (pinfunction "C24_C24") (pintype "passive"))
      (node (ref "X5") (pin "C24") (pinfunction "C24_C24") (pintype "passive"))
      (node (ref "X6") (pin "C24") (pinfunction "C24_C24") (pintype "passive"))
      (node (ref "X7") (pin "C24") (pinfunction "C24_C24") (pintype "passive"))
      (node (ref "X8") (pin "C24") (pinfunction "C24_C24") (pintype "passive"))
    )
    (net (code "32") (name "GPIO.23") (class "Default")
      (node (ref "SV1") (pin "50") (pinfunction "50_50") (pintype "passive"))
      (node (ref "SV2") (pin "50") (pinfunction "50_50") (pintype "passive"))
      (node (ref "X1") (pin "C25") (pinfunction "C25_C25") (pintype "passive"))
      (node (ref "X2") (pin "C25") (pinfunction "C25_C25") (pintype "passive"))
      (node (ref "X3") (pin "C25") (pinfunction "C25_C25") (pintype "passive"))
      (node (ref "X4") (pin "C25") (pinfunction "C25_C25") (pintype "passive"))
      (node (ref "X5") (pin "C25") (pinfunction "C25_C25") (pintype "passive"))
      (node (ref "X6") (pin "C25") (pinfunction "C25_C25") (pintype "passive"))
      (node (ref "X7") (pin "C25") (pinfunction "C25_C25") (pintype "passive"))
      (node (ref "X8") (pin "C25") (pinfunction "C25_C25") (pintype "passive"))
    )
    (net (code "33") (name "GPIO.24") (class "Default")
      (node (ref "SV1") (pin "52") (pinfunction "52_52") (pintype "passive"))
      (node (ref "SV2") (pin "52") (pinfunction "52_52") (pintype "passive"))
      (node (ref "X1") (pin "C26") (pinfunction "C26_C26") (pintype "passive"))
      (node (ref "X2") (pin "C26") (pinfunction "C26_C26") (pintype "passive"))
      (node (ref "X3") (pin "C26") (pinfunction "C26_C26") (pintype "passive"))
      (node (ref "X4") (pin "C26") (pinfunction "C26_C26") (pintype "passive"))
      (node (ref "X5") (pin "C26") (pinfunction "C26_C26") (pintype "passive"))
      (node (ref "X6") (pin "C26") (pinfunction "C26_C26") (pintype "passive"))
      (node (ref "X7") (pin "C26") (pinfunction "C26_C26") (pintype "passive"))
      (node (ref "X8") (pin "C26") (pinfunction "C26_C26") (pintype "passive"))
    )
    (net (code "34") (name "GPIO.25") (class "Default")
      (node (ref "SV1") (pin "54") (pinfunction "54_54") (pintype "passive"))
      (node (ref "SV2") (pin "54") (pinfunction "54_54") (pintype "passive"))
      (node (ref "X1") (pin "C27") (pinfunction "C27_C27") (pintype "passive"))
      (node (ref "X2") (pin "C27") (pinfunction "C27_C27") (pintype "passive"))
      (node (ref "X3") (pin "C27") (pinfunction "C27_C27") (pintype "passive"))
      (node (ref "X4") (pin "C27") (pinfunction "C27_C27") (pintype "passive"))
      (node (ref "X5") (pin "C27") (pinfunction "C27_C27") (pintype "passive"))
      (node (ref "X6") (pin "C27") (pinfunction "C27_C27") (pintype "passive"))
      (node (ref "X7") (pin "C27") (pinfunction "C27_C27") (pintype "passive"))
      (node (ref "X8") (pin "C27") (pinfunction "C27_C27") (pintype "passive"))
    )
    (net (code "35") (name "I2C_SCL") (class "Default")
      (node (ref "SV1") (pin "10") (pinfunction "10_10") (pintype "passive"))
      (node (ref "SV1") (pin "9") (pinfunction "9_9") (pintype "passive"))
      (node (ref "SV2") (pin "10") (pinfunction "10_10") (pintype "passive"))
      (node (ref "SV2") (pin "9") (pinfunction "9_9") (pintype "passive"))
      (node (ref "X1") (pin "A5") (pinfunction "A5_A5") (pintype "passive"))
      (node (ref "X1") (pin "C5") (pinfunction "C5_C5") (pintype "passive"))
      (node (ref "X2") (pin "A5") (pinfunction "A5_A5") (pintype "passive"))
      (node (ref "X2") (pin "C5") (pinfunction "C5_C5") (pintype "passive"))
      (node (ref "X3") (pin "A5") (pinfunction "A5_A5") (pintype "passive"))
      (node (ref "X3") (pin "C5") (pinfunction "C5_C5") (pintype "passive"))
      (node (ref "X4") (pin "A5") (pinfunction "A5_A5") (pintype "passive"))
      (node (ref "X4") (pin "C5") (pinfunction "C5_C5") (pintype "passive"))
      (node (ref "X5") (pin "A5") (pinfunction "A5_A5") (pintype "passive"))
      (node (ref "X5") (pin "C5") (pinfunction "C5_C5") (pintype "passive"))
      (node (ref "X6") (pin "A5") (pinfunction "A5_A5") (pintype "passive"))
      (node (ref "X6") (pin "C5") (pinfunction "C5_C5") (pintype "passive"))
      (node (ref "X7") (pin "A5") (pinfunction "A5_A5") (pintype "passive"))
      (node (ref "X7") (pin "C5") (pinfunction "C5_C5") (pintype "passive"))
      (node (ref "X8") (pin "A5") (pinfunction "A5_A5") (pintype "passive"))
      (node (ref "X8") (pin "C5") (pinfunction "C5_C5") (pintype "passive"))
    )
    (net (code "36") (name "I2C_SDA") (class "Default")
      (node (ref "SV1") (pin "7") (pinfunction "7_7") (pintype "passive"))
      (node (ref "SV1") (pin "8") (pinfunction "8_8") (pintype "passive"))
      (node (ref "SV2") (pin "7") (pinfunction "7_7") (pintype "passive"))
      (node (ref "SV2") (pin "8") (pinfunction "8_8") (pintype "passive"))
      (node (ref "X1") (pin "A4") (pinfunction "A4_A4") (pintype "passive"))
      (node (ref "X1") (pin "C4") (pinfunction "C4_C4") (pintype "passive"))
      (node (ref "X2") (pin "A4") (pinfunction "A4_A4") (pintype "passive"))
      (node (ref "X2") (pin "C4") (pinfunction "C4_C4") (pintype "passive"))
      (node (ref "X3") (pin "A4") (pinfunction "A4_A4") (pintype "passive"))
      (node (ref "X3") (pin "C4") (pinfunction "C4_C4") (pintype "passive"))
      (node (ref "X4") (pin "A4") (pinfunction "A4_A4") (pintype "passive"))
      (node (ref "X4") (pin "C4") (pinfunction "C4_C4") (pintype "passive"))
      (node (ref "X5") (pin "A4") (pinfunction "A4_A4") (pintype "passive"))
      (node (ref "X5") (pin "C4") (pinfunction "C4_C4") (pintype "passive"))
      (node (ref "X6") (pin "A4") (pinfunction "A4_A4") (pintype "passive"))
      (node (ref "X6") (pin "C4") (pinfunction "C4_C4") (pintype "passive"))
      (node (ref "X7") (pin "A4") (pinfunction "A4_A4") (pintype "passive"))
      (node (ref "X7") (pin "C4") (pinfunction "C4_C4") (pintype "passive"))
      (node (ref "X8") (pin "A4") (pinfunction "A4_A4") (pintype "passive"))
      (node (ref "X8") (pin "C4") (pinfunction "C4_C4") (pintype "passive"))
    )
    (net (code "37") (name "PI_RXD") (class "Default")
      (node (ref "SV1") (pin "24") (pinfunction "24_24") (pintype "passive"))
      (node (ref "SV2") (pin "24") (pinfunction "24_24") (pintype "passive"))
      (node (ref "X1") (pin "C12") (pinfunction "C12_C12") (pintype "passive"))
      (node (ref "X2") (pin "C12") (pinfunction "C12_C12") (pintype "passive"))
      (node (ref "X3") (pin "C12") (pinfunction "C12_C12") (pintype "passive"))
      (node (ref "X4") (pin "C12") (pinfunction "C12_C12") (pintype "passive"))
      (node (ref "X5") (pin "C12") (pinfunction "C12_C12") (pintype "passive"))
      (node (ref "X6") (pin "C12") (pinfunction "C12_C12") (pintype "passive"))
      (node (ref "X7") (pin "C12") (pinfunction "C12_C12") (pintype "passive"))
      (node (ref "X8") (pin "C12") (pinfunction "C12_C12") (pintype "passive"))
    )
    (net (code "38") (name "PI_TXD") (class "Default")
      (node (ref "SV1") (pin "23") (pinfunction "23_23") (pintype "passive"))
      (node (ref "SV2") (pin "23") (pinfunction "23_23") (pintype "passive"))
      (node (ref "X1") (pin "A12") (pinfunction "A12_A12") (pintype "passive"))
      (node (ref "X2") (pin "A12") (pinfunction "A12_A12") (pintype "passive"))
      (node (ref "X3") (pin "A12") (pinfunction "A12_A12") (pintype "passive"))
      (node (ref "X4") (pin "A12") (pinfunction "A12_A12") (pintype "passive"))
      (node (ref "X5") (pin "A12") (pinfunction "A12_A12") (pintype "passive"))
      (node (ref "X6") (pin "A12") (pinfunction "A12_A12") (pintype "passive"))
      (node (ref "X7") (pin "A12") (pinfunction "A12_A12") (pintype "passive"))
      (node (ref "X8") (pin "A12") (pinfunction "A12_A12") (pintype "passive"))
    )
    (net (code "39") (name "SPI_CE0") (class "Default")
      (node (ref "SV1") (pin "19") (pinfunction "19_19") (pintype "passive"))
      (node (ref "SV2") (pin "19") (pinfunction "19_19") (pintype "passive"))
      (node (ref "X1") (pin "A10") (pinfunction "A10_A10") (pintype "passive"))
      (node (ref "X2") (pin "A10") (pinfunction "A10_A10") (pintype "passive"))
      (node (ref "X3") (pin "A10") (pinfunction "A10_A10") (pintype "passive"))
      (node (ref "X4") (pin "A10") (pinfunction "A10_A10") (pintype "passive"))
      (node (ref "X5") (pin "A10") (pinfunction "A10_A10") (pintype "passive"))
      (node (ref "X6") (pin "A10") (pinfunction "A10_A10") (pintype "passive"))
      (node (ref "X7") (pin "A10") (pinfunction "A10_A10") (pintype "passive"))
      (node (ref "X8") (pin "A10") (pinfunction "A10_A10") (pintype "passive"))
    )
    (net (code "40") (name "SPI_CE1") (class "Default")
      (node (ref "SV1") (pin "22") (pinfunction "22_22") (pintype "passive"))
      (node (ref "SV2") (pin "22") (pinfunction "22_22") (pintype "passive"))
      (node (ref "X1") (pin "C11") (pinfunction "C11_C11") (pintype "passive"))
      (node (ref "X2") (pin "C11") (pinfunction "C11_C11") (pintype "passive"))
      (node (ref "X3") (pin "C11") (pinfunction "C11_C11") (pintype "passive"))
      (node (ref "X4") (pin "C11") (pinfunction "C11_C11") (pintype "passive"))
      (node (ref "X5") (pin "C11") (pinfunction "C11_C11") (pintype "passive"))
      (node (ref "X6") (pin "C11") (pinfunction "C11_C11") (pintype "passive"))
      (node (ref "X7") (pin "C11") (pinfunction "C11_C11") (pintype "passive"))
      (node (ref "X8") (pin "C11") (pinfunction "C11_C11") (pintype "passive"))
    )
    (net (code "41") (name "SPI_MISO") (class "Default")
      (node (ref "SV1") (pin "17") (pinfunction "17_17") (pintype "passive"))
      (node (ref "SV2") (pin "17") (pinfunction "17_17") (pintype "passive"))
      (node (ref "X1") (pin "A9") (pinfunction "A9_A9") (pintype "passive"))
      (node (ref "X2") (pin "A9") (pinfunction "A9_A9") (pintype "passive"))
      (node (ref "X3") (pin "A9") (pinfunction "A9_A9") (pintype "passive"))
      (node (ref "X4") (pin "A9") (pinfunction "A9_A9") (pintype "passive"))
      (node (ref "X5") (pin "A9") (pinfunction "A9_A9") (pintype "passive"))
      (node (ref "X6") (pin "A9") (pinfunction "A9_A9") (pintype "passive"))
      (node (ref "X7") (pin "A9") (pinfunction "A9_A9") (pintype "passive"))
      (node (ref "X8") (pin "A9") (pinfunction "A9_A9") (pintype "passive"))
    )
    (net (code "42") (name "SPI_MOSI") (class "Default")
      (node (ref "SV1") (pin "18") (pinfunction "18_18") (pintype "passive"))
      (node (ref "SV2") (pin "18") (pinfunction "18_18") (pintype "passive"))
      (node (ref "X1") (pin "C9") (pinfunction "C9_C9") (pintype "passive"))
      (node (ref "X2") (pin "C9") (pinfunction "C9_C9") (pintype "passive"))
      (node (ref "X3") (pin "C9") (pinfunction "C9_C9") (pintype "passive"))
      (node (ref "X4") (pin "C9") (pinfunction "C9_C9") (pintype "passive"))
      (node (ref "X5") (pin "C9") (pinfunction "C9_C9") (pintype "passive"))
      (node (ref "X6") (pin "C9") (pinfunction "C9_C9") (pintype "passive"))
      (node (ref "X7") (pin "C9") (pinfunction "C9_C9") (pintype "passive"))
      (node (ref "X8") (pin "C9") (pinfunction "C9_C9") (pintype "passive"))
    )
    (net (code "43") (name "SPI_SCLK") (class "Default")
      (node (ref "SV1") (pin "20") (pinfunction "20_20") (pintype "passive"))
      (node (ref "SV2") (pin "20") (pinfunction "20_20") (pintype "passive"))
      (node (ref "X1") (pin "C10") (pinfunction "C10_C10") (pintype "passive"))
      (node (ref "X2") (pin "C10") (pinfunction "C10_C10") (pintype "passive"))
      (node (ref "X3") (pin "C10") (pinfunction "C10_C10") (pintype "passive"))
      (node (ref "X4") (pin "C10") (pinfunction "C10_C10") (pintype "passive"))
      (node (ref "X5") (pin "C10") (pinfunction "C10_C10") (pintype "passive"))
      (node (ref "X6") (pin "C10") (pinfunction "C10_C10") (pintype "passive"))
      (node (ref "X7") (pin "C10") (pinfunction "C10_C10") (pintype "passive"))
      (node (ref "X8") (pin "C10") (pinfunction "C10_C10") (pintype "passive"))
    )
    (net (code "44") (name "~{PI_RESET}") (class "Default")
      (node (ref "SV1") (pin "51") (pinfunction "51_51") (pintype "passive"))
      (node (ref "SV2") (pin "51") (pinfunction "51_51") (pintype "passive"))
      (node (ref "X1") (pin "A26") (pinfunction "A26_A26") (pintype "passive"))
      (node (ref "X2") (pin "A26") (pinfunction "A26_A26") (pintype "passive"))
      (node (ref "X3") (pin "A26") (pinfunction "A26_A26") (pintype "passive"))
      (node (ref "X4") (pin "A26") (pinfunction "A26_A26") (pintype "passive"))
      (node (ref "X5") (pin "A26") (pinfunction "A26_A26") (pintype "passive"))
      (node (ref "X6") (pin "A26") (pinfunction "A26_A26") (pintype "passive"))
      (node (ref "X7") (pin "A26") (pinfunction "A26_A26") (pintype "passive"))
      (node (ref "X8") (pin "A26") (pinfunction "A26_A26") (pintype "passive"))
    )
  )
)
